# Crystal.net
KiCad netlist of a schematic drawn in Altium Designer
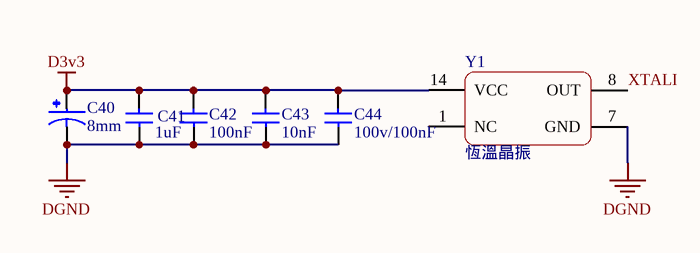
[diagram p0: Crystal.SchDoc]

(export (version "E")
  (design (tool "Eeschema 10.0.6"))
  (components
    (comp (ref "C40")
      (value "8mm")
      (footprint "CAP_dual")
      (description "8mm cap")
      (libsource (lib "Switch_Schlib") (part "dip-cap"))
    )
    (comp (ref "C41")
      (value "1uF")
      (footprint "C-0603")
      (description "C-0603")
      (libsource (lib "Switch_Schlib") (part "C-0603"))
    )
    (comp (ref "C42")
      (value "100nF")
      (footprint "C-0603")
      (description "C-0603")
      (libsource (lib "Switch_Schlib") (part "C-0603"))
    )
    (comp (ref "C43")
      (value "10nF")
      (footprint "C-0603")
      (description "C-0603")
      (libsource (lib "Switch_Schlib") (part "C-0603"))
    )
    (comp (ref "C44")
      (value "100v/100nF")
      (footprint "100v0.1u")
      (description "plastic capacitor")
      (libsource (lib "Switch_Schlib") (part "plastic cap"))
    )
    (comp (ref "Y1") (value "恆溫晶振") (footprint "恆溫晶振") (libsource (lib "Switch_Schlib") (part "恆溫晶振")))
  )
  (nets
    (net (code "1") (name "/XTALI") (class "Default")
      (node (ref "Y1") (pin "8") (pinfunction "OUT_8") (pintype "passive"))
    )
    (net (code "2") (name "D3v3") (class "Default")
      (node (ref "C40") (pin "1") (pinfunction "1_1") (pintype "passive"))
      (node (ref "C41") (pin "2") (pintype "passive"))
      (node (ref "C42") (pin "2") (pintype "passive"))
      (node (ref "C43") (pin "2") (pintype "passive"))
      (node (ref "C44") (pin "2") (pintype "passive"))
      (node (ref "Y1") (pin "14") (pinfunction "VCC_14") (pintype "passive"))
    )
    (net (code "3") (name "DGND") (class "Default")
      (node (ref "C40") (pin "2") (pinfunction "2_2") (pintype "passive"))
      (node (ref "C41") (pin "1") (pintype "passive"))
      (node (ref "C42") (pin "1") (pintype "passive"))
      (node (ref "C43") (pin "1") (pintype "passive"))
      (node (ref "C44") (pin "1") (pintype "passive"))
      (node (ref "Y1") (pin "7") (pinfunction "GND_7") (pintype "passive"))
    )
    (net (code "4") (name "unconnected-(Y1-NC-Pad1)") (class "Default")
      (node (ref "Y1") (pin "1") (pinfunction "NC_1") (pintype "passive"))
    )
  )
)
